# GSRv3_2.net
KiCad netlist of a schematic drawn in EAGLE
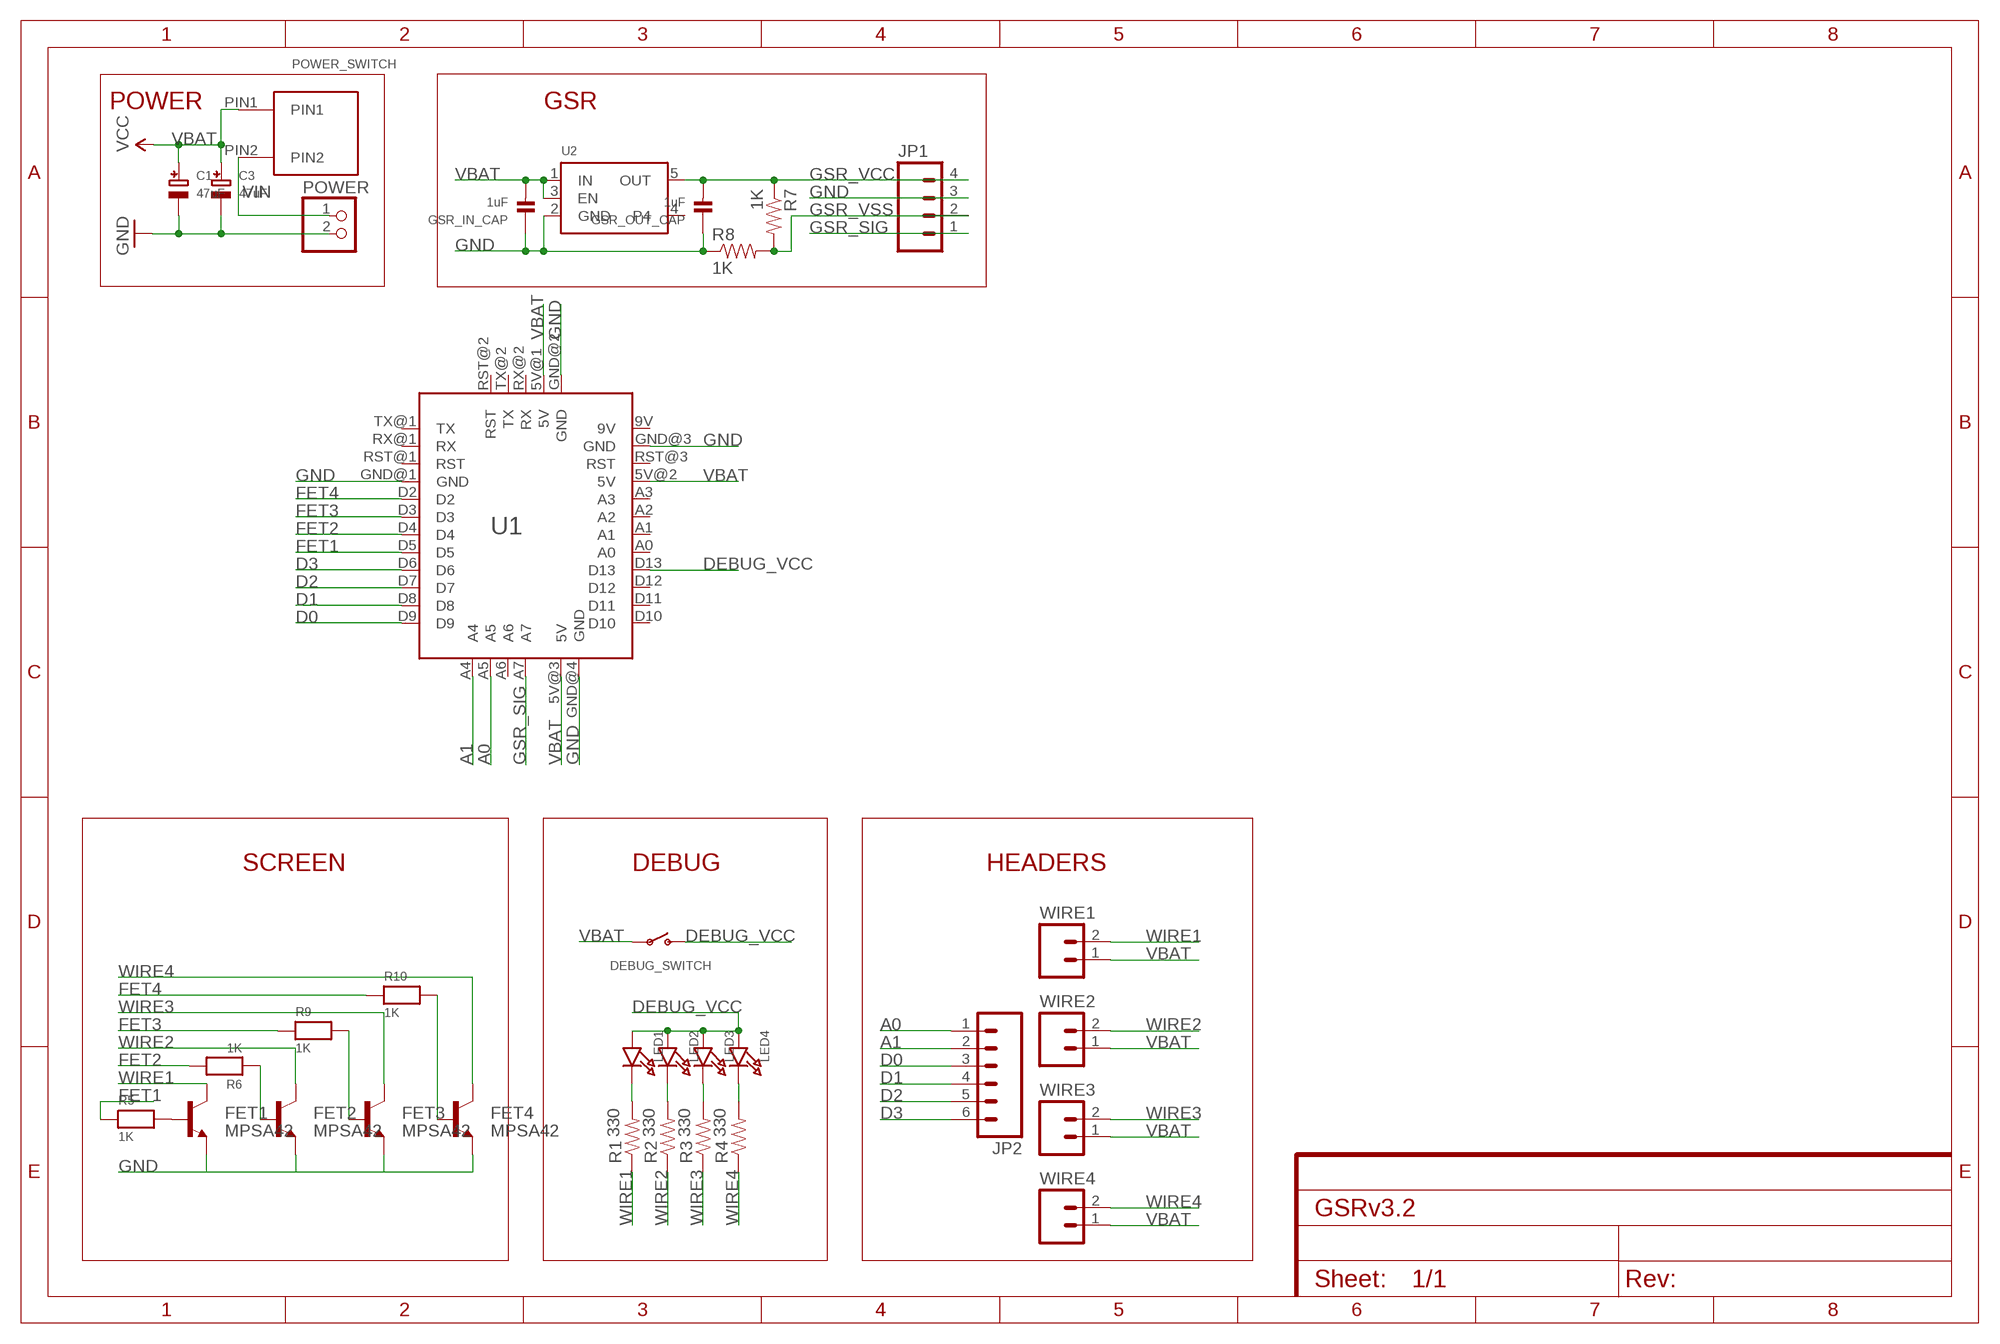
[diagram p0: schematic, sheet 1]

(export (version "E")
  (design (tool "Eeschema 10.0.6"))
  (components
    (comp (ref "C1")
      (value "47uF")
      (footprint "eagle-import:EIA3528-21_B-W")
      (libsource (lib "eagle-import") (part "CAP_TANTALUMB/3528_WAVE"))
    )
    (comp (ref "C3")
      (value "47uF")
      (footprint "eagle-import:EIA3528-21_B-W")
      (libsource (lib "eagle-import") (part "CAP_TANTALUMB/3528_WAVE"))
    )
    (comp (ref "DEBUG_SWITCH")
      (value "SWITCH_SPST")
      (footprint "eagle-import:SPST_SMT_19192")
      (libsource (lib "eagle-import") (part "SWITCH_SPST"))
    )
    (comp (ref "FET1")
      (value "MPSA42")
      (footprint "eagle-import:SOT23-3")
      (libsource (lib "eagle-import") (part "TRANSISTOR_NPNMPSA42"))
    )
    (comp (ref "FET2")
      (value "MPSA42")
      (footprint "eagle-import:SOT23-3")
      (libsource (lib "eagle-import") (part "TRANSISTOR_NPNMPSA42"))
    )
    (comp (ref "FET3")
      (value "MPSA42")
      (footprint "eagle-import:SOT23-3")
      (libsource (lib "eagle-import") (part "TRANSISTOR_NPNMPSA42"))
    )
    (comp (ref "FET4")
      (value "MPSA42")
      (footprint "eagle-import:SOT23-3")
      (libsource (lib "eagle-import") (part "TRANSISTOR_NPNMPSA42"))
    )
    (comp (ref "GSR_IN_CAP")
      (value "1uF")
      (footprint "eagle-import:0603")
      (libsource (lib "eagle-import") (part "CAP_CERAMIC0603"))
    )
    (comp (ref "GSR_OUT_CAP")
      (value "1uF")
      (footprint "eagle-import:0603")
      (libsource (lib "eagle-import") (part "CAP_CERAMIC0603"))
    )
    (comp (ref "JP1")
      (value "M04POLAR")
      (footprint "eagle-import:MOLEX-1X4")
      (libsource (lib "eagle-import") (part "M04POLAR"))
    )
    (comp (ref "JP2")
      (value "M06SILK_FEMALE_PTH")
      (footprint "eagle-import:1X06")
      (libsource (lib "eagle-import") (part "M06SILK_FEMALE_PTH"))
    )
    (comp (ref "LED1")
      (value "LED0603_NOOUTLINE")
      (footprint "eagle-import:CHIPLED_0603_NOOUTLINE")
      (libsource (lib "eagle-import") (part "LED0603_NOOUTLINE"))
    )
    (comp (ref "LED2")
      (value "LED0603_NOOUTLINE")
      (footprint "eagle-import:CHIPLED_0603_NOOUTLINE")
      (libsource (lib "eagle-import") (part "LED0603_NOOUTLINE"))
    )
    (comp (ref "LED3")
      (value "LED0603_NOOUTLINE")
      (footprint "eagle-import:CHIPLED_0603_NOOUTLINE")
      (libsource (lib "eagle-import") (part "LED0603_NOOUTLINE"))
    )
    (comp (ref "LED4")
      (value "LED0603_NOOUTLINE")
      (footprint "eagle-import:CHIPLED_0603_NOOUTLINE")
      (libsource (lib "eagle-import") (part "LED0603_NOOUTLINE"))
    )
    (comp (ref "POWER")
      (value "JST_2PIN")
      (footprint "eagle-import:JSTPH2")
      (libsource (lib "eagle-import") (part "JST_2PIN"))
    )
    (comp (ref "POWER_SWITCH")
      (value "PUSH_BUTTON")
      (footprint "eagle-import:PUSH_BUTTON")
      (libsource (lib "eagle-import") (part "PUSH_BUTTON"))
    )
    (comp (ref "R1")
      (value "330")
      (footprint "eagle-import:0603-RES")
      (libsource (lib "eagle-import") (part "RESISTOR0603-RES"))
    )
    (comp (ref "R2")
      (value "330")
      (footprint "eagle-import:0603-RES")
      (libsource (lib "eagle-import") (part "RESISTOR0603-RES"))
    )
    (comp (ref "R3")
      (value "330")
      (footprint "eagle-import:0603-RES")
      (libsource (lib "eagle-import") (part "RESISTOR0603-RES"))
    )
    (comp (ref "R4")
      (value "330")
      (footprint "eagle-import:0603-RES")
      (libsource (lib "eagle-import") (part "RESISTOR0603-RES"))
    )
    (comp (ref "R5")
      (value "1K")
      (footprint "eagle-import:0603")
      (libsource (lib "eagle-import") (part "RESISTOR0603"))
    )
    (comp (ref "R6")
      (value "1K")
      (footprint "eagle-import:0603")
      (libsource (lib "eagle-import") (part "RESISTOR0603"))
    )
    (comp (ref "R7")
      (value "1K")
      (footprint "eagle-import:0603")
      (libsource (lib "eagle-import") (part "0OHM-1/10W-5%(0603)"))
    )
    (comp (ref "R8")
      (value "1K")
      (footprint "eagle-import:0603")
      (libsource (lib "eagle-import") (part "0OHM-1/10W-5%(0603)"))
    )
    (comp (ref "R9")
      (value "1K")
      (footprint "eagle-import:0603")
      (libsource (lib "eagle-import") (part "RESISTOR0603"))
    )
    (comp (ref "R10")
      (value "1K")
      (footprint "eagle-import:0603")
      (libsource (lib "eagle-import") (part "RESISTOR0603"))
    )
    (comp (ref "U1")
      (value "ARDUINO_MINI")
      (footprint "eagle-import:ARDUINO_MINI")
      (libsource (lib "eagle-import") (part "ARDUINO_MINI"))
    )
    (comp (ref "U2")
      (value "VREG_SOT23-5")
      (footprint "eagle-import:SOT23-5")
      (libsource (lib "eagle-import") (part "VREG_SOT23-5"))
    )
    (comp (ref "WIRE1")
      (value "M02POLAR")
      (footprint "eagle-import:MOLEX-1X2")
      (libsource (lib "eagle-import") (part "M02POLAR"))
    )
    (comp (ref "WIRE2")
      (value "M02POLAR")
      (footprint "eagle-import:MOLEX-1X2")
      (libsource (lib "eagle-import") (part "M02POLAR"))
    )
    (comp (ref "WIRE3")
      (value "M02POLAR")
      (footprint "eagle-import:MOLEX-1X2")
      (libsource (lib "eagle-import") (part "M02POLAR"))
    )
    (comp (ref "WIRE4")
      (value "M02POLAR")
      (footprint "eagle-import:MOLEX-1X2")
      (libsource (lib "eagle-import") (part "M02POLAR"))
    )
  )
  (nets
    (net (code "1") (name "/9V") (class "Default")
      (node (ref "U1") (pin "9V") (pinfunction "9V_9V") (pintype "power_in"))
    )
    (net (code "2") (name "/A0") (class "Default")
      (node (ref "JP2") (pin "1") (pinfunction "1_1") (pintype "passive"))
      (node (ref "U1") (pin "A5") (pinfunction "A5_A5") (pintype "bidirectional"))
    )
    (net (code "3") (name "/A1") (class "Default")
      (node (ref "JP2") (pin "2") (pinfunction "2_2") (pintype "passive"))
      (node (ref "U1") (pin "A4") (pinfunction "A4_A4") (pintype "bidirectional"))
    )
    (net (code "4") (name "/D0") (class "Default")
      (node (ref "JP2") (pin "3") (pinfunction "3_3") (pintype "passive"))
      (node (ref "U1") (pin "D9") (pinfunction "D9_D9") (pintype "bidirectional"))
    )
    (net (code "5") (name "/D1") (class "Default")
      (node (ref "JP2") (pin "4") (pinfunction "4_4") (pintype "passive"))
      (node (ref "U1") (pin "D8") (pinfunction "D8_D8") (pintype "bidirectional"))
    )
    (net (code "6") (name "/D2") (class "Default")
      (node (ref "JP2") (pin "5") (pinfunction "5_5") (pintype "passive"))
      (node (ref "U1") (pin "D7") (pinfunction "D7_D7") (pintype "bidirectional"))
    )
    (net (code "7") (name "/D3") (class "Default")
      (node (ref "JP2") (pin "6") (pinfunction "6_6") (pintype "passive"))
      (node (ref "U1") (pin "D6") (pinfunction "D6_D6") (pintype "bidirectional"))
    )
    (net (code "8") (name "/DEBUG_VCC") (class "Default")
      (node (ref "DEBUG_SWITCH") (pin "C") (pinfunction "S_C") (pintype "passive"))
      (node (ref "LED1") (pin "A") (pinfunction "A_A") (pintype "passive"))
      (node (ref "LED2") (pin "A") (pinfunction "A_A") (pintype "passive"))
      (node (ref "LED3") (pin "A") (pinfunction "A_A") (pintype "passive"))
      (node (ref "LED4") (pin "A") (pinfunction "A_A") (pintype "passive"))
      (node (ref "U1") (pin "D13") (pinfunction "D13_D13") (pintype "bidirectional"))
    )
    (net (code "9") (name "/FET1") (class "Default")
      (node (ref "R5") (pin "1") (pinfunction "1_1") (pintype "passive"))
      (node (ref "U1") (pin "D5") (pinfunction "D5_D5") (pintype "bidirectional"))
    )
    (net (code "10") (name "/FET2") (class "Default")
      (node (ref "R6") (pin "2") (pinfunction "2_2") (pintype "passive"))
      (node (ref "U1") (pin "D4") (pinfunction "D4_D4") (pintype "bidirectional"))
    )
    (net (code "11") (name "/FET3") (class "Default")
      (node (ref "R9") (pin "1") (pinfunction "1_1") (pintype "passive"))
      (node (ref "U1") (pin "D3") (pinfunction "D3_D3") (pintype "bidirectional"))
    )
    (net (code "12") (name "/FET4") (class "Default")
      (node (ref "R10") (pin "1") (pinfunction "1_1") (pintype "passive"))
      (node (ref "U1") (pin "D2") (pinfunction "D2_D2") (pintype "bidirectional"))
    )
    (net (code "13") (name "/GSR_SIG") (class "Default")
      (node (ref "JP1") (pin "1") (pinfunction "1_1") (pintype "passive"))
      (node (ref "U1") (pin "A7") (pinfunction "A7_A7") (pintype "bidirectional"))
    )
    (net (code "14") (name "/GSR_VCC") (class "Default")
      (node (ref "GSR_OUT_CAP") (pin "2") (pinfunction "P$2_2") (pintype "passive"))
      (node (ref "JP1") (pin "4") (pinfunction "4_4") (pintype "passive"))
      (node (ref "R7") (pin "1") (pinfunction "1_1") (pintype "passive"))
      (node (ref "U2") (pin "5") (pinfunction "OUT_5") (pintype "bidirectional"))
    )
    (net (code "15") (name "/GSR_VSS") (class "Default")
      (node (ref "JP1") (pin "2") (pinfunction "2_2") (pintype "passive"))
      (node (ref "R7") (pin "2") (pinfunction "2_2") (pintype "passive"))
      (node (ref "R8") (pin "2") (pinfunction "2_2") (pintype "passive"))
    )
    (net (code "16") (name "/VIN") (class "Default")
      (node (ref "POWER") (pin "1") (pinfunction "1_1") (pintype "passive"))
      (node (ref "POWER_SWITCH") (pin "PIN2") (pinfunction "PIN2_PIN2") (pintype "bidirectional"))
    )
    (net (code "17") (name "/WIRE1") (class "Default")
      (node (ref "FET1") (pin "3") (pinfunction "C_3") (pintype "passive"))
      (node (ref "R1") (pin "1") (pinfunction "1_1") (pintype "passive"))
      (node (ref "WIRE1") (pin "2") (pinfunction "2_2") (pintype "passive"))
    )
    (net (code "18") (name "/WIRE2") (class "Default")
      (node (ref "FET2") (pin "3") (pinfunction "C_3") (pintype "passive"))
      (node (ref "R2") (pin "1") (pinfunction "1_1") (pintype "passive"))
      (node (ref "WIRE2") (pin "2") (pinfunction "2_2") (pintype "passive"))
    )
    (net (code "19") (name "/WIRE3") (class "Default")
      (node (ref "FET3") (pin "3") (pinfunction "C_3") (pintype "passive"))
      (node (ref "R3") (pin "1") (pinfunction "1_1") (pintype "passive"))
      (node (ref "WIRE3") (pin "2") (pinfunction "2_2") (pintype "passive"))
    )
    (net (code "20") (name "/WIRE4") (class "Default")
      (node (ref "FET4") (pin "3") (pinfunction "C_3") (pintype "passive"))
      (node (ref "R4") (pin "1") (pinfunction "1_1") (pintype "passive"))
      (node (ref "WIRE4") (pin "2") (pinfunction "2_2") (pintype "passive"))
    )
    (net (code "21") (name "GND") (class "Default")
      (node (ref "C1") (pin "-") (pinfunction "-_-") (pintype "passive"))
      (node (ref "C3") (pin "-") (pinfunction "-_-") (pintype "passive"))
      (node (ref "FET1") (pin "2") (pinfunction "E_2") (pintype "passive"))
      (node (ref "FET2") (pin "2") (pinfunction "E_2") (pintype "passive"))
      (node (ref "FET3") (pin "2") (pinfunction "E_2") (pintype "passive"))
      (node (ref "FET4") (pin "2") (pinfunction "E_2") (pintype "passive"))
      (node (ref "GSR_IN_CAP") (pin "1") (pinfunction "P$1_1") (pintype "passive"))
      (node (ref "GSR_OUT_CAP") (pin "1") (pinfunction "P$1_1") (pintype "passive"))
      (node (ref "JP1") (pin "3") (pinfunction "3_3") (pintype "passive"))
      (node (ref "POWER") (pin "2") (pinfunction "2_2") (pintype "passive"))
      (node (ref "R8") (pin "1") (pinfunction "1_1") (pintype "passive"))
      (node (ref "U1") (pin "GND@1") (pinfunction "GND_GND@1") (pintype "power_in"))
      (node (ref "U1") (pin "GND@2") (pinfunction "GND_GND@2") (pintype "power_in"))
      (node (ref "U1") (pin "GND@3") (pinfunction "GND_GND@3") (pintype "power_in"))
      (node (ref "U1") (pin "GND@4") (pinfunction "GND_GND@4") (pintype "power_in"))
      (node (ref "U2") (pin "2") (pinfunction "GND_2") (pintype "bidirectional"))
    )
    (net (code "22") (name "Net-(FET1-B)") (class "Default")
      (node (ref "FET1") (pin "1") (pinfunction "B_1") (pintype "passive"))
      (node (ref "R5") (pin "2") (pinfunction "2_2") (pintype "passive"))
    )
    (net (code "23") (name "Net-(FET2-B)") (class "Default")
      (node (ref "FET2") (pin "1") (pinfunction "B_1") (pintype "passive"))
      (node (ref "R6") (pin "1") (pinfunction "1_1") (pintype "passive"))
    )
    (net (code "24") (name "Net-(FET3-B)") (class "Default")
      (node (ref "FET3") (pin "1") (pinfunction "B_1") (pintype "passive"))
      (node (ref "R9") (pin "2") (pinfunction "2_2") (pintype "passive"))
    )
    (net (code "25") (name "Net-(FET4-B)") (class "Default")
      (node (ref "FET4") (pin "1") (pinfunction "B_1") (pintype "passive"))
      (node (ref "R10") (pin "2") (pinfunction "2_2") (pintype "passive"))
    )
    (net (code "26") (name "Net-(LED1-PadC)") (class "Default")
      (node (ref "LED1") (pin "C") (pinfunction "C_C") (pintype "passive"))
      (node (ref "R1") (pin "2") (pinfunction "2_2") (pintype "passive"))
    )
    (net (code "27") (name "Net-(LED2-PadC)") (class "Default")
      (node (ref "LED2") (pin "C") (pinfunction "C_C") (pintype "passive"))
      (node (ref "R2") (pin "2") (pinfunction "2_2") (pintype "passive"))
    )
    (net (code "28") (name "Net-(LED3-PadC)") (class "Default")
      (node (ref "LED3") (pin "C") (pinfunction "C_C") (pintype "passive"))
      (node (ref "R3") (pin "2") (pinfunction "2_2") (pintype "passive"))
    )
    (net (code "29") (name "Net-(LED4-PadC)") (class "Default")
      (node (ref "LED4") (pin "C") (pinfunction "C_C") (pintype "passive"))
      (node (ref "R4") (pin "2") (pinfunction "2_2") (pintype "passive"))
    )
    (net (code "30") (name "VCC") (class "Default")
      (node (ref "C1") (pin "+") (pinfunction "+_+") (pintype "passive"))
      (node (ref "C3") (pin "+") (pinfunction "+_+") (pintype "passive"))
      (node (ref "DEBUG_SWITCH") (pin "B") (pinfunction "P_B") (pintype "passive"))
      (node (ref "GSR_IN_CAP") (pin "2") (pinfunction "P$2_2") (pintype "passive"))
      (node (ref "POWER_SWITCH") (pin "PIN1") (pinfunction "PIN1_PIN1") (pintype "bidirectional"))
      (node (ref "U1") (pin "5V@1") (pinfunction "5V_5V@1") (pintype "power_in"))
      (node (ref "U1") (pin "5V@2") (pinfunction "5V_5V@2") (pintype "power_in"))
      (node (ref "U1") (pin "5V@3") (pinfunction "5V_5V@3") (pintype "power_in"))
      (node (ref "U2") (pin "1") (pinfunction "IN_1") (pintype "bidirectional"))
      (node (ref "U2") (pin "3") (pinfunction "EN_3") (pintype "bidirectional"))
      (node (ref "WIRE1") (pin "1") (pinfunction "1_1") (pintype "passive"))
      (node (ref "WIRE2") (pin "1") (pinfunction "1_1") (pintype "passive"))
      (node (ref "WIRE3") (pin "1") (pinfunction "1_1") (pintype "passive"))
      (node (ref "WIRE4") (pin "1") (pinfunction "1_1") (pintype "passive"))
    )
    (net (code "31") (name "unconnected-(U1-PadA0)") (class "Default")
      (node (ref "U1") (pin "A0") (pinfunction "A0_A0") (pintype "bidirectional"))
    )
    (net (code "32") (name "unconnected-(U1-PadA1)") (class "Default")
      (node (ref "U1") (pin "A1") (pinfunction "A1_A1") (pintype "bidirectional"))
    )
    (net (code "33") (name "unconnected-(U1-PadA2)") (class "Default")
      (node (ref "U1") (pin "A2") (pinfunction "A2_A2") (pintype "bidirectional"))
    )
    (net (code "34") (name "unconnected-(U1-PadA3)") (class "Default")
      (node (ref "U1") (pin "A3") (pinfunction "A3_A3") (pintype "bidirectional"))
    )
    (net (code "35") (name "unconnected-(U1-PadA6)") (class "Default")
      (node (ref "U1") (pin "A6") (pinfunction "A6_A6") (pintype "bidirectional"))
    )
    (net (code "36") (name "unconnected-(U1-PadD10)") (class "Default")
      (node (ref "U1") (pin "D10") (pinfunction "D10_D10") (pintype "bidirectional"))
    )
    (net (code "37") (name "unconnected-(U1-PadD11)") (class "Default")
      (node (ref "U1") (pin "D11") (pinfunction "D11_D11") (pintype "bidirectional"))
    )
    (net (code "38") (name "unconnected-(U1-PadD12)") (class "Default")
      (node (ref "U1") (pin "D12") (pinfunction "D12_D12") (pintype "bidirectional"))
    )
    (net (code "39") (name "unconnected-(U1-RST-PadRST@1)") (class "Default")
      (node (ref "U1") (pin "RST@1") (pinfunction "RST_RST@1") (pintype "bidirectional"))
    )
    (net (code "40") (name "unconnected-(U1-RST-PadRST@2)") (class "Default")
      (node (ref "U1") (pin "RST@2") (pinfunction "RST_RST@2") (pintype "bidirectional"))
    )
    (net (code "41") (name "unconnected-(U1-RST-PadRST@3)") (class "Default")
      (node (ref "U1") (pin "RST@3") (pinfunction "RST_RST@3") (pintype "bidirectional"))
    )
    (net (code "42") (name "unconnected-(U1-RX-PadRX@1)") (class "Default")
      (node (ref "U1") (pin "RX@1") (pinfunction "RX_RX@1") (pintype "bidirectional"))
    )
    (net (code "43") (name "unconnected-(U1-RX-PadRX@2)") (class "Default")
      (node (ref "U1") (pin "RX@2") (pinfunction "RX_RX@2") (pintype "bidirectional"))
    )
    (net (code "44") (name "unconnected-(U1-TX-PadTX@1)") (class "Default")
      (node (ref "U1") (pin "TX@1") (pinfunction "TX_TX@1") (pintype "bidirectional"))
    )
    (net (code "45") (name "unconnected-(U1-TX-PadTX@2)") (class "Default")
      (node (ref "U1") (pin "TX@2") (pinfunction "TX_TX@2") (pintype "bidirectional"))
    )
    (net (code "46") (name "unconnected-(U2-P4-Pad4)") (class "Default")
      (node (ref "U2") (pin "4") (pinfunction "P4_4") (pintype "bidirectional"))
    )
  )
)
